# TOFSensorControl.net
KiCad netlist of a schematic drawn in Altium Designer
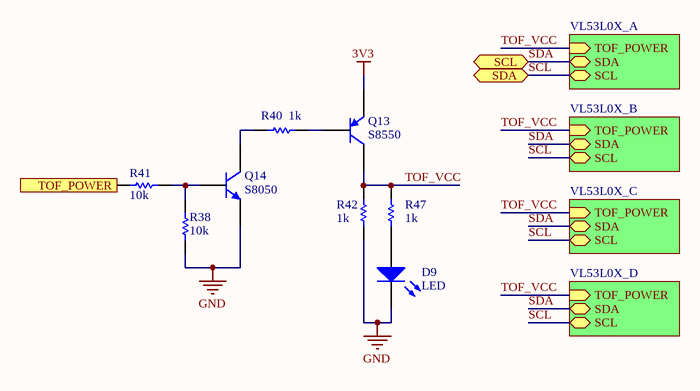
[diagram p0: TOFSensorControl.SchDoc]

(export (version "E")
  (design (tool "Eeschema 10.0.6"))
  (components
    (comp (ref "D9")
      (value "LED")
      (footprint "J1-0603 LED")
      (fields (field (name "PUBLISHER") "Altium Limited"))
      (libsource (lib "sumo") (part "LED"))
    )
    (comp (ref "Q13")
      (value "S8550")
      (footprint "SOT23-3M")
      (description "PNP General Purpose Amplifier")
      (fields (field (name "PUBLISHER") "Altium Limited"))
      (libsource (lib "sumo") (part "S8550"))
    )
    (comp (ref "Q14")
      (value "S8050")
      (footprint "SOT23-3M")
      (description "NPN General Purpose Amplifier")
      (fields (field (name "PUBLISHER") "Altium Limited"))
      (libsource (lib "sumo") (part "S8050"))
    )
    (comp (ref "R38")
      (value "10k")
      (footprint "J1-0603")
      (description "Resistor")
      (fields (field (name "Comment") "Res1") (field (name "PUBLISHER") "Altium Limited"))
      (libsource (lib "Miscellaneous Devices") (part "Res1"))
    )
    (comp (ref "R40")
      (value "1k")
      (footprint "J1-0603")
      (description "Resistor")
      (fields (field (name "Comment") "Res1") (field (name "PUBLISHER") "Altium Limited"))
      (libsource (lib "Miscellaneous Devices") (part "Res1"))
    )
    (comp (ref "R41")
      (value "10k")
      (footprint "J1-0603")
      (description "Resistor")
      (fields (field (name "Comment") "Res1") (field (name "PUBLISHER") "Altium Limited"))
      (libsource (lib "Miscellaneous Devices") (part "Res1"))
    )
    (comp (ref "R42")
      (value "1k")
      (footprint "J1-0603")
      (description "Resistor")
      (fields (field (name "Comment") "Res1") (field (name "PUBLISHER") "Altium Limited"))
      (libsource (lib "Miscellaneous Devices") (part "Res1"))
    )
    (comp (ref "R47")
      (value "1k")
      (footprint "J1-0603")
      (description "Resistor")
      (fields (field (name "Comment") "Res1") (field (name "PUBLISHER") "Altium Limited"))
      (libsource (lib "Miscellaneous Devices") (part "Res1"))
    )
  )
  (nets
    (net (code "2") (name "/TOF_POWER") (class "Default")
      (node (ref "R41") (pin "2") (pinfunction "2_2") (pintype "passive"))
    )
    (net (code "3") (name "/TOF_VCC") (class "Default")
      (node (ref "Q13") (pin "3") (pinfunction "C_3") (pintype "passive"))
      (node (ref "R42") (pin "2") (pinfunction "2_2") (pintype "passive"))
      (node (ref "R47") (pin "2") (pinfunction "2_2") (pintype "passive"))
    )
    (net (code "4") (name "3V3") (class "Default")
      (node (ref "Q13") (pin "2") (pinfunction "E_2") (pintype "passive"))
    )
    (net (code "5") (name "GND") (class "Default")
      (node (ref "D9") (pin "2") (pinfunction "K_2") (pintype "passive"))
      (node (ref "Q14") (pin "2") (pinfunction "E_2") (pintype "passive"))
      (node (ref "R38") (pin "2") (pinfunction "2_2") (pintype "passive"))
      (node (ref "R42") (pin "1") (pinfunction "1_1") (pintype "passive"))
    )
    (net (code "6") (name "Net-(D9-A)") (class "Default")
      (node (ref "D9") (pin "1") (pinfunction "A_1") (pintype "passive"))
      (node (ref "R47") (pin "1") (pinfunction "1_1") (pintype "passive"))
    )
    (net (code "7") (name "Net-(Q13-B)") (class "Default")
      (node (ref "Q13") (pin "1") (pinfunction "B_1") (pintype "passive"))
      (node (ref "R40") (pin "1") (pinfunction "1_1") (pintype "passive"))
    )
    (net (code "8") (name "Net-(Q14-B)") (class "Default")
      (node (ref "Q14") (pin "1") (pinfunction "B_1") (pintype "passive"))
      (node (ref "R38") (pin "1") (pinfunction "1_1") (pintype "passive"))
      (node (ref "R41") (pin "1") (pinfunction "1_1") (pintype "passive"))
    )
    (net (code "9") (name "Net-(Q14-C)") (class "Default")
      (node (ref "Q14") (pin "3") (pinfunction "C_3") (pintype "passive"))
      (node (ref "R40") (pin "2") (pinfunction "2_2") (pintype "passive"))
    )
  )
)
